# autoimpedance.net
KiCad netlist of a schematic drawn in EAGLE
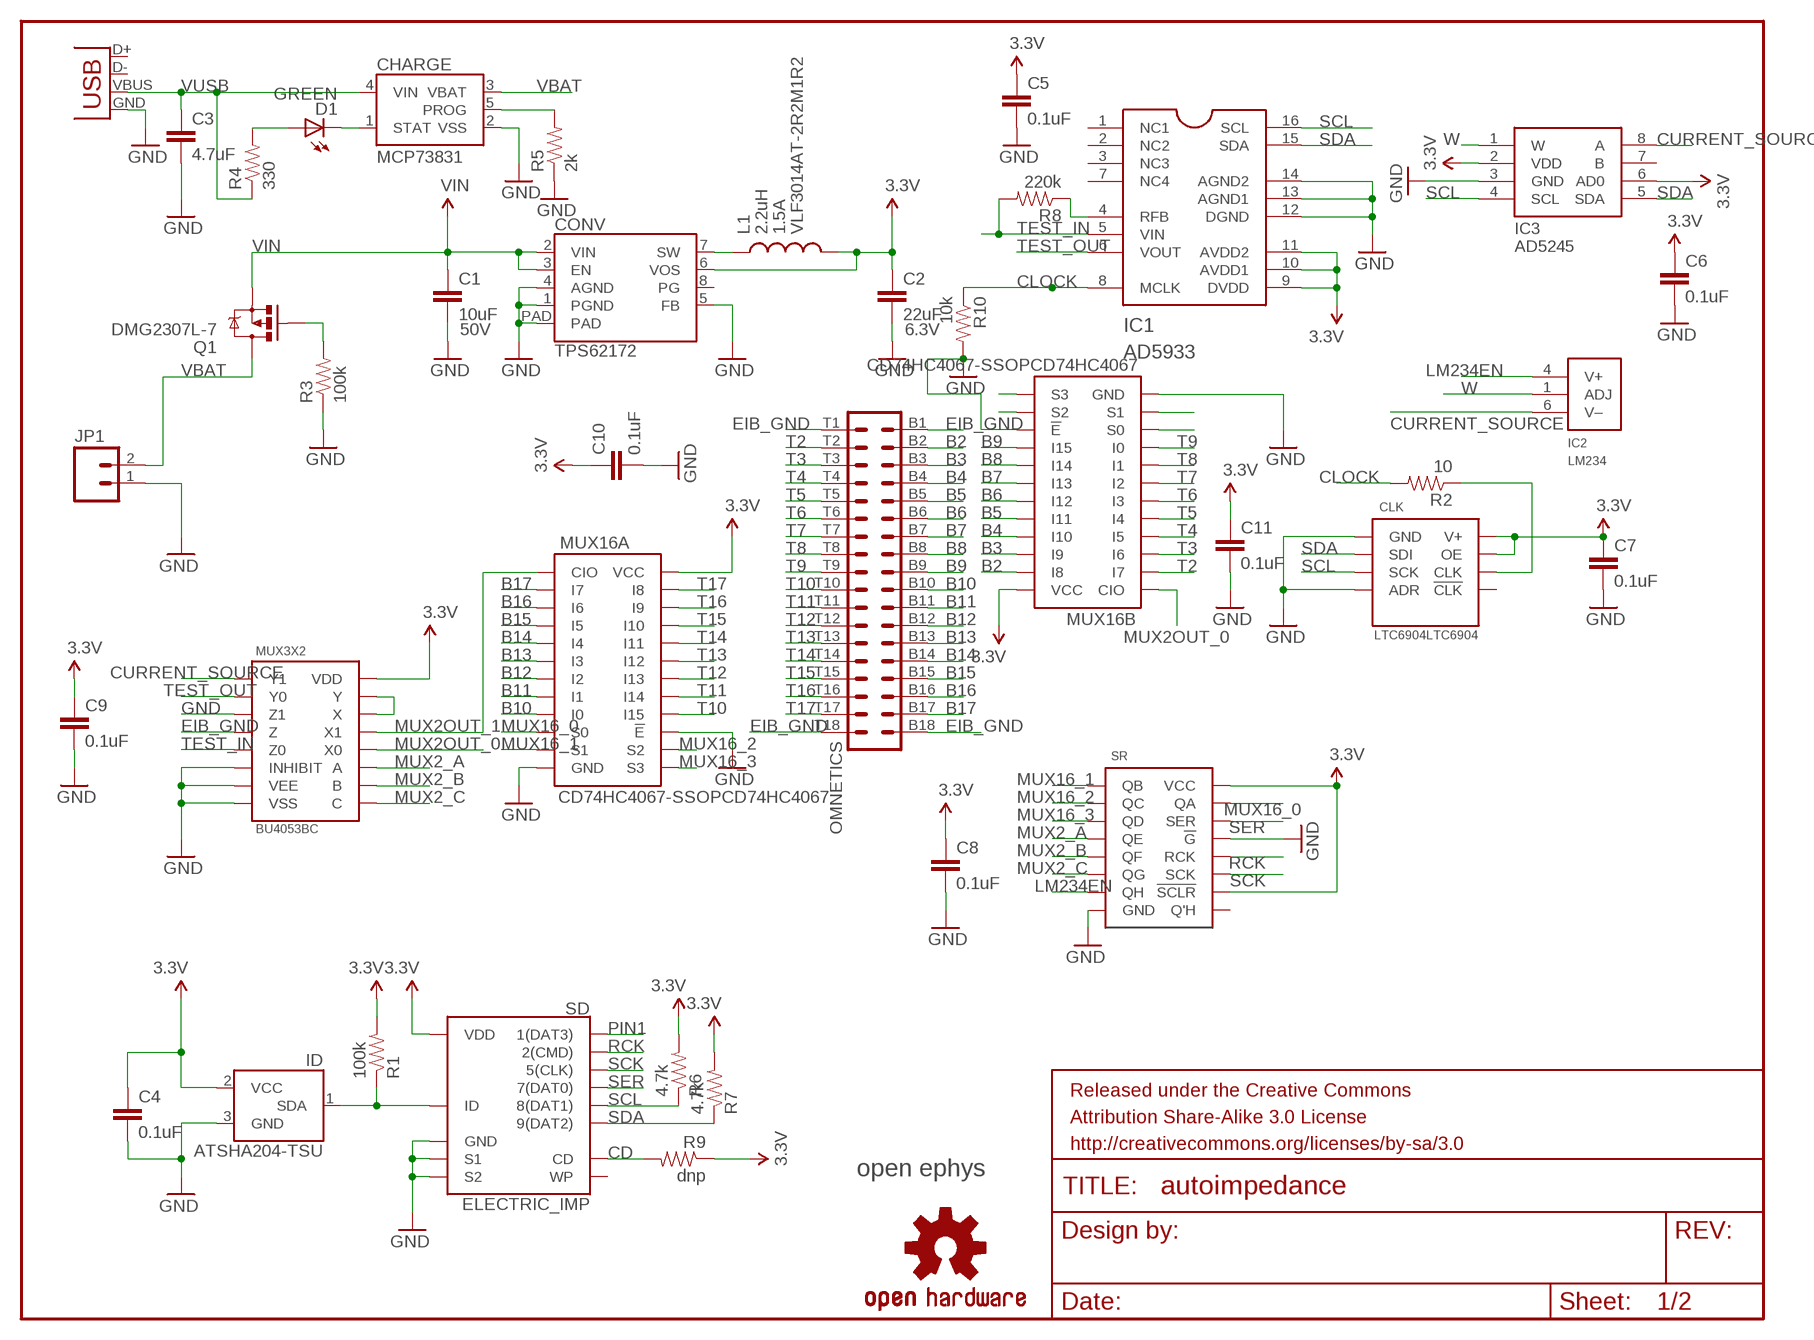
[diagram p0: schematic, sheet 1]

(export (version "E")
  (design (tool "Eeschema 10.0.6"))
  (components
    (comp (ref "C1")
      (value "10uF")
      (footprint "eagle-import:1210")
      (libsource (lib "eagle-import") (part "SparkFun-Passives_CAP1210"))
    )
    (comp (ref "C2")
      (value "22uF")
      (footprint "eagle-import:0805")
      (libsource (lib "eagle-import") (part "SparkFun-Passives_CAP0805"))
    )
    (comp (ref "C3")
      (value "4.7uF")
      (footprint "eagle-import:1210")
      (libsource (lib "eagle-import") (part "SparkFun-Passives_CAP1210"))
    )
    (comp (ref "C4")
      (value "0.1uF")
      (footprint "eagle-import:0603-CAP")
      (libsource (lib "eagle-import") (part "CAP0603-CAP"))
    )
    (comp (ref "C5")
      (value "0.1uF")
      (footprint "eagle-import:0603-CAP")
      (libsource (lib "eagle-import") (part "CAP0603-CAP"))
    )
    (comp (ref "C6")
      (value "0.1uF")
      (footprint "eagle-import:0603-CAP")
      (libsource (lib "eagle-import") (part "CAP0603-CAP"))
    )
    (comp (ref "C7")
      (value "0.1uF")
      (footprint "eagle-import:0603-CAP")
      (libsource (lib "eagle-import") (part "CAP0603-CAP"))
    )
    (comp (ref "C8")
      (value "0.1uF")
      (footprint "eagle-import:0603-CAP")
      (libsource (lib "eagle-import") (part "CAP0603-CAP"))
    )
    (comp (ref "C9")
      (value "0.1uF")
      (footprint "eagle-import:0603-CAP")
      (libsource (lib "eagle-import") (part "CAP0603-CAP"))
    )
    (comp (ref "C10")
      (value "0.1uF")
      (footprint "eagle-import:0603-CAP")
      (libsource (lib "eagle-import") (part "CAP0603-CAP"))
    )
    (comp (ref "C11")
      (value "0.1uF")
      (footprint "eagle-import:0603-CAP")
      (libsource (lib "eagle-import") (part "CAP0603-CAP"))
    )
    (comp (ref "CHARGE")
      (value "MCP73831")
      (footprint "eagle-import:SOT23-5")
      (libsource (lib "eagle-import") (part "MCP73831"))
    )
    (comp (ref "CLK")
      (value "LTC6904LTC6904")
      (footprint "eagle-import:MSOP08")
      (libsource (lib "eagle-import") (part "LTC6904LTC6904"))
    )
    (comp (ref "CONV")
      (value "TPS62172")
      (footprint "eagle-import:WSON-8-PAD")
      (libsource (lib "eagle-import") (part "TPS62172"))
    )
    (comp (ref "D1")
      (value "GREEN")
      (footprint "eagle-import:LED-0603")
      (libsource (lib "eagle-import") (part "LED-GREEN0603"))
    )
    (comp (ref "FRAME1")
      (value "FRAME-LETTER")
      (footprint "eagle-import:CREATIVE_COMMONS")
      (libsource (lib "eagle-import") (part "FRAME-LETTER"))
    )
    (comp (ref "IC1")
      (value "AD5933")
      (footprint "eagle-import:AD5933")
      (libsource (lib "eagle-import") (part "AD5933"))
    )
    (comp (ref "IC2")
      (value "LM234")
      (footprint "eagle-import:LM234")
      (libsource (lib "eagle-import") (part "LM234"))
    )
    (comp (ref "IC3")
      (value "AD5245")
      (footprint "eagle-import:AD5245")
      (libsource (lib "eagle-import") (part "AD5245"))
    )
    (comp (ref "ID")
      (value "ATSHA204-TSU")
      (footprint "eagle-import:SOT23-3")
      (libsource (lib "eagle-import") (part "ATSHA204-TSU"))
    )
    (comp (ref "JP1")
      (value "M02SMD")
      (footprint "eagle-import:1X02_SMD")
      (libsource (lib "eagle-import") (part "M02SMD"))
    )
    (comp (ref "L1")
      (value "2.2uH")
      (footprint "eagle-import:VLF4012A")
      (libsource (lib "eagle-import") (part "INDUCTORVLF4012A"))
    )
    (comp (ref "MUX3X2")
      (value "BU4053BC")
      (footprint "eagle-import:SSOP16")
      (libsource (lib "eagle-import") (part "BU4053BC"))
    )
    (comp (ref "MUX16A")
      (value "CD74HC4067-SSOPCD74HC4067")
      (footprint "eagle-import:SSOP24")
      (libsource (lib "eagle-import") (part "CD74HC4067-SSOPCD74HC4067"))
    )
    (comp (ref "MUX16B")
      (value "CD74HC4067-SSOPCD74HC4067")
      (footprint "eagle-import:SSOP24")
      (libsource (lib "eagle-import") (part "CD74HC4067-SSOPCD74HC4067"))
    )
    (comp (ref "OMNETICS")
      (value "OMNETICS_A79025")
      (footprint "eagle-import:OMNETICS_A79025")
      (libsource (lib "eagle-import") (part "OMNETICS_A79025"))
    )
    (comp (ref "Q1")
      (value "DMG2307L-7")
      (footprint "eagle-import:SOT23-3")
      (libsource (lib "eagle-import") (part "MOSFET-PCHANNELSMD"))
    )
    (comp (ref "R1")
      (value "100k")
      (footprint "eagle-import:0402-RES")
      (libsource (lib "eagle-import") (part "RESISTOR0402-RES"))
    )
    (comp (ref "R2")
      (value "10")
      (footprint "eagle-import:0402-RES")
      (libsource (lib "eagle-import") (part "RESISTOR0402-RES"))
    )
    (comp (ref "R3")
      (value "100k")
      (footprint "eagle-import:0402-RES")
      (libsource (lib "eagle-import") (part "RESISTOR0402-RES"))
    )
    (comp (ref "R4")
      (value "330")
      (footprint "eagle-import:0402-RES")
      (libsource (lib "eagle-import") (part "RESISTOR0402-RES"))
    )
    (comp (ref "R5")
      (value "2k")
      (footprint "eagle-import:0402-RES")
      (libsource (lib "eagle-import") (part "RESISTOR0402-RES"))
    )
    (comp (ref "R6")
      (value "4.7k")
      (footprint "eagle-import:0402-RES")
      (libsource (lib "eagle-import") (part "RESISTOR0402-RES"))
    )
    (comp (ref "R7")
      (value "4.7k")
      (footprint "eagle-import:0402-RES")
      (libsource (lib "eagle-import") (part "RESISTOR0402-RES"))
    )
    (comp (ref "R8")
      (value "220k")
      (footprint "eagle-import:0402-RES")
      (libsource (lib "eagle-import") (part "RESISTOR0402-RES"))
    )
    (comp (ref "R9")
      (value "dnp")
      (footprint "eagle-import:0402-RES")
      (libsource (lib "eagle-import") (part "RESISTOR0402-RES"))
    )
    (comp (ref "R10")
      (value "10k")
      (footprint "eagle-import:0402-RES")
      (libsource (lib "eagle-import") (part "RESISTOR0402-RES"))
    )
    (comp (ref "SD")
      (value "ELECTRIC_IMP")
      (footprint "eagle-import:SD_MMC_SOCKET")
      (libsource (lib "eagle-import") (part "ELECTRIC_IMP"))
    )
    (comp (ref "SR")
      (value "MM74HC595MM74HC595")
      (footprint "eagle-import:TSSOP16")
      (libsource (lib "eagle-import") (part "MM74HC595MM74HC595"))
    )
    (comp (ref "U$5")
      (value "OSHW-LOGOS")
      (footprint "eagle-import:OSHW-LOGO-S")
      (libsource (lib "eagle-import") (part "OSHW-LOGOS"))
    )
    (comp (ref "U$7")
      (value "OPEN_EPHYS_LOGO")
      (footprint "eagle-import:OPEN_EPHYS_LOGO")
      (libsource (lib "eagle-import") (part "OPEN_EPHYS_LOGO"))
    )
    (comp (ref "USB")
      (value "USBSMD")
      (footprint "eagle-import:USB-MINIB")
      (libsource (lib "eagle-import") (part "USBSMD"))
    )
  )
  (nets
    (net (code "1") (name "3.3V") (class "Default")
      (node (ref "C10") (pin "1") (pinfunction "1_1") (pintype "passive"))
      (node (ref "C11") (pin "1") (pinfunction "1_1") (pintype "passive"))
      (node (ref "C2") (pin "1") (pinfunction "1_1") (pintype "passive"))
      (node (ref "C4") (pin "1") (pinfunction "1_1") (pintype "passive"))
      (node (ref "C5") (pin "1") (pinfunction "1_1") (pintype "passive"))
      (node (ref "C6") (pin "1") (pinfunction "1_1") (pintype "passive"))
      (node (ref "C7") (pin "1") (pinfunction "1_1") (pintype "passive"))
      (node (ref "C8") (pin "1") (pinfunction "1_1") (pintype "passive"))
      (node (ref "C9") (pin "1") (pinfunction "1_1") (pintype "passive"))
      (node (ref "CLK") (pin "7") (pinfunction "OE_7") (pintype "bidirectional"))
      (node (ref "CLK") (pin "8") (pinfunction "V+_8") (pintype "power_in"))
      (node (ref "CONV") (pin "6") (pinfunction "VOS_6") (pintype "bidirectional"))
      (node (ref "IC1") (pin "10") (pinfunction "AVDD1_10") (pintype "bidirectional"))
      (node (ref "IC1") (pin "11") (pinfunction "AVDD2_11") (pintype "bidirectional"))
      (node (ref "IC1") (pin "9") (pinfunction "DVDD_9") (pintype "bidirectional"))
      (node (ref "IC3") (pin "2") (pinfunction "VDD_2") (pintype "bidirectional"))
      (node (ref "IC3") (pin "6") (pinfunction "AD0_6") (pintype "bidirectional"))
      (node (ref "ID") (pin "2") (pinfunction "VCC_2") (pintype "bidirectional"))
      (node (ref "L1") (pin "P$2") (pinfunction "2_P$2") (pintype "passive"))
      (node (ref "MUX16A") (pin "24") (pinfunction "VCC_24") (pintype "power_in"))
      (node (ref "MUX16B") (pin "24") (pinfunction "VCC_24") (pintype "power_in"))
      (node (ref "MUX3X2") (pin "16") (pinfunction "VDD_16") (pintype "input"))
      (node (ref "R1") (pin "2") (pinfunction "2_2") (pintype "passive"))
      (node (ref "R6") (pin "2") (pinfunction "2_2") (pintype "passive"))
      (node (ref "R7") (pin "2") (pinfunction "2_2") (pintype "passive"))
      (node (ref "R9") (pin "1") (pinfunction "1_1") (pintype "passive"))
      (node (ref "SD") (pin "4") (pinfunction "VDD_4") (pintype "bidirectional"))
      (node (ref "SR") (pin "10") (pinfunction "~{SCLR}_10") (pintype "bidirectional"))
      (node (ref "SR") (pin "16") (pinfunction "VCC_16") (pintype "power_in"))
    )
    (net (code "2") (name "B2") (class "Default")
      (node (ref "MUX16B") (pin "23") (pinfunction "I8_23") (pintype "bidirectional"))
      (node (ref "OMNETICS") (pin "B2") (pinfunction "B2_B2") (pintype "passive"))
    )
    (net (code "3") (name "B3") (class "Default")
      (node (ref "MUX16B") (pin "22") (pinfunction "I9_22") (pintype "bidirectional"))
      (node (ref "OMNETICS") (pin "B3") (pinfunction "B3_B3") (pintype "passive"))
    )
    (net (code "4") (name "B4") (class "Default")
      (node (ref "MUX16B") (pin "21") (pinfunction "I10_21") (pintype "bidirectional"))
      (node (ref "OMNETICS") (pin "B4") (pinfunction "B4_B4") (pintype "passive"))
    )
    (net (code "5") (name "B5") (class "Default")
      (node (ref "MUX16B") (pin "20") (pinfunction "I11_20") (pintype "bidirectional"))
      (node (ref "OMNETICS") (pin "B5") (pinfunction "B5_B5") (pintype "passive"))
    )
    (net (code "6") (name "B6") (class "Default")
      (node (ref "MUX16B") (pin "19") (pinfunction "I12_19") (pintype "bidirectional"))
      (node (ref "OMNETICS") (pin "B6") (pinfunction "B6_B6") (pintype "passive"))
    )
    (net (code "7") (name "B7") (class "Default")
      (node (ref "MUX16B") (pin "18") (pinfunction "I13_18") (pintype "bidirectional"))
      (node (ref "OMNETICS") (pin "B7") (pinfunction "B7_B7") (pintype "passive"))
    )
    (net (code "8") (name "B8") (class "Default")
      (node (ref "MUX16B") (pin "17") (pinfunction "I14_17") (pintype "bidirectional"))
      (node (ref "OMNETICS") (pin "B8") (pinfunction "B8_B8") (pintype "passive"))
    )
    (net (code "9") (name "B9") (class "Default")
      (node (ref "MUX16B") (pin "16") (pinfunction "I15_16") (pintype "bidirectional"))
      (node (ref "OMNETICS") (pin "B9") (pinfunction "B9_B9") (pintype "passive"))
    )
    (net (code "10") (name "B10") (class "Default")
      (node (ref "MUX16A") (pin "9") (pinfunction "I0_9") (pintype "bidirectional"))
      (node (ref "OMNETICS") (pin "B10") (pinfunction "B10_B10") (pintype "passive"))
    )
    (net (code "11") (name "B11") (class "Default")
      (node (ref "MUX16A") (pin "8") (pinfunction "I1_8") (pintype "bidirectional"))
      (node (ref "OMNETICS") (pin "B11") (pinfunction "B11_B11") (pintype "passive"))
    )
    (net (code "12") (name "B12") (class "Default")
      (node (ref "MUX16A") (pin "7") (pinfunction "I2_7") (pintype "bidirectional"))
      (node (ref "OMNETICS") (pin "B12") (pinfunction "B12_B12") (pintype "passive"))
    )
    (net (code "13") (name "B13") (class "Default")
      (node (ref "MUX16A") (pin "6") (pinfunction "I3_6") (pintype "bidirectional"))
      (node (ref "OMNETICS") (pin "B13") (pinfunction "B13_B13") (pintype "passive"))
    )
    (net (code "14") (name "B14") (class "Default")
      (node (ref "MUX16A") (pin "5") (pinfunction "I4_5") (pintype "bidirectional"))
      (node (ref "OMNETICS") (pin "B14") (pinfunction "B14_B14") (pintype "passive"))
    )
    (net (code "15") (name "B15") (class "Default")
      (node (ref "MUX16A") (pin "4") (pinfunction "I5_4") (pintype "bidirectional"))
      (node (ref "OMNETICS") (pin "B15") (pinfunction "B15_B15") (pintype "passive"))
    )
    (net (code "16") (name "B16") (class "Default")
      (node (ref "MUX16A") (pin "3") (pinfunction "I6_3") (pintype "bidirectional"))
      (node (ref "OMNETICS") (pin "B16") (pinfunction "B16_B16") (pintype "passive"))
    )
    (net (code "17") (name "B17") (class "Default")
      (node (ref "MUX16A") (pin "2") (pinfunction "I7_2") (pintype "bidirectional"))
      (node (ref "OMNETICS") (pin "B17") (pinfunction "B17_B17") (pintype "passive"))
    )
    (net (code "18") (name "CD") (class "Default")
      (node (ref "R9") (pin "2") (pinfunction "2_2") (pintype "passive"))
      (node (ref "SD") (pin "CD") (pinfunction "CD_CD") (pintype "bidirectional"))
    )
    (net (code "19") (name "CLOCK") (class "Default")
      (node (ref "IC1") (pin "8") (pinfunction "MCLK_8") (pintype "bidirectional"))
      (node (ref "R10") (pin "1") (pinfunction "1_1") (pintype "passive"))
      (node (ref "R2") (pin "2") (pinfunction "2_2") (pintype "passive"))
    )
    (net (code "20") (name "CURRENT_SOURCE") (class "Default")
      (node (ref "IC2") (pin "6") (pinfunction "V–_6") (pintype "bidirectional"))
      (node (ref "IC3") (pin "8") (pinfunction "A_8") (pintype "bidirectional"))
      (node (ref "MUX3X2") (pin "1") (pinfunction "Y1_1") (pintype "bidirectional"))
    )
    (net (code "21") (name "EIB_GND") (class "Default")
      (node (ref "MUX3X2") (pin "4") (pinfunction "Z_4") (pintype "bidirectional"))
      (node (ref "OMNETICS") (pin "B1") (pinfunction "B1_B1") (pintype "passive"))
      (node (ref "OMNETICS") (pin "B18") (pinfunction "B18_B18") (pintype "passive"))
      (node (ref "OMNETICS") (pin "T1") (pinfunction "T1_T1") (pintype "passive"))
      (node (ref "OMNETICS") (pin "T18") (pinfunction "T18_T18") (pintype "passive"))
    )
    (net (code "22") (name "GND") (class "Default")
      (node (ref "C1") (pin "2") (pinfunction "2_2") (pintype "passive"))
      (node (ref "C10") (pin "2") (pinfunction "2_2") (pintype "passive"))
      (node (ref "C11") (pin "2") (pinfunction "2_2") (pintype "passive"))
      (node (ref "C2") (pin "2") (pinfunction "2_2") (pintype "passive"))
      (node (ref "C3") (pin "2") (pinfunction "2_2") (pintype "passive"))
      (node (ref "C4") (pin "2") (pinfunction "2_2") (pintype "passive"))
      (node (ref "C5") (pin "2") (pinfunction "2_2") (pintype "passive"))
      (node (ref "C6") (pin "2") (pinfunction "2_2") (pintype "passive"))
      (node (ref "C7") (pin "2") (pinfunction "2_2") (pintype "passive"))
      (node (ref "C8") (pin "2") (pinfunction "2_2") (pintype "passive"))
      (node (ref "C9") (pin "2") (pinfunction "2_2") (pintype "passive"))
      (node (ref "CHARGE") (pin "2") (pinfunction "VSS_2") (pintype "power_in"))
      (node (ref "CLK") (pin "1") (pinfunction "GND_1") (pintype "power_in"))
      (node (ref "CLK") (pin "4") (pinfunction "ADR_4") (pintype "bidirectional"))
      (node (ref "CONV") (pin "1") (pinfunction "PGND_1") (pintype "bidirectional"))
      (node (ref "CONV") (pin "4") (pinfunction "AGND_4") (pintype "bidirectional"))
      (node (ref "CONV") (pin "5") (pinfunction "FB_5") (pintype "bidirectional"))
      (node (ref "CONV") (pin "PAD") (pinfunction "PAD_PAD") (pintype "bidirectional"))
      (node (ref "IC1") (pin "12") (pinfunction "DGND_12") (pintype "bidirectional"))
      (node (ref "IC1") (pin "13") (pinfunction "AGND1_13") (pintype "bidirectional"))
      (node (ref "IC1") (pin "14") (pinfunction "AGND2_14") (pintype "bidirectional"))
      (node (ref "IC3") (pin "3") (pinfunction "GND_3") (pintype "bidirectional"))
      (node (ref "ID") (pin "3") (pinfunction "GND_3") (pintype "bidirectional"))
      (node (ref "JP1") (pin "1") (pinfunction "1_1") (pintype "passive"))
      (node (ref "MUX16A") (pin "12") (pinfunction "GND_12") (pintype "power_in"))
      (node (ref "MUX16A") (pin "15") (pinfunction "~{E}_15") (pintype "bidirectional"))
      (node (ref "MUX16B") (pin "12") (pinfunction "GND_12") (pintype "power_in"))
      (node (ref "MUX16B") (pin "15") (pinfunction "~{E}_15") (pintype "bidirectional"))
      (node (ref "MUX3X2") (pin "3") (pinfunction "Z1_3") (pintype "bidirectional"))
      (node (ref "MUX3X2") (pin "6") (pinfunction "INHIBIT_6") (pintype "bidirectional"))
      (node (ref "MUX3X2") (pin "7") (pinfunction "VEE_7") (pintype "power_in"))
      (node (ref "MUX3X2") (pin "8") (pinfunction "VSS_8") (pintype "power_in"))
      (node (ref "R10") (pin "2") (pinfunction "2_2") (pintype "passive"))
      (node (ref "R3") (pin "1") (pinfunction "1_1") (pintype "passive"))
      (node (ref "R5") (pin "1") (pinfunction "1_1") (pintype "passive"))
      (node (ref "SD") (pin "3") (pinfunction "GND_3") (pintype "bidirectional"))
      (node (ref "SD") (pin "S1") (pinfunction "S1_S1") (pintype "bidirectional"))
      (node (ref "SD") (pin "S2") (pinfunction "S2_S2") (pintype "bidirectional"))
      (node (ref "SR") (pin "13") (pinfunction "~{G}_13") (pintype "bidirectional"))
      (node (ref "SR") (pin "8") (pinfunction "GND_8") (pintype "power_in"))
      (node (ref "USB") (pin "GND") (pinfunction "GND_GND") (pintype "bidirectional"))
    )
    (net (code "23") (name "LM234EN") (class "Default")
      (node (ref "IC2") (pin "4") (pinfunction "V+_4") (pintype "bidirectional"))
      (node (ref "SR") (pin "7") (pinfunction "QH_7") (pintype "output"))
    )
    (net (code "24") (name "MUX2OUT_0") (class "Default")
      (node (ref "MUX16B") (pin "1") (pinfunction "CIO_1") (pintype "bidirectional"))
      (node (ref "MUX3X2") (pin "12") (pinfunction "X0_12") (pintype "bidirectional"))
    )
    (net (code "25") (name "MUX2OUT_1") (class "Default")
      (node (ref "MUX16A") (pin "1") (pinfunction "CIO_1") (pintype "bidirectional"))
      (node (ref "MUX3X2") (pin "13") (pinfunction "X1_13") (pintype "bidirectional"))
    )
    (net (code "26") (name "MUX2_A") (class "Default")
      (node (ref "MUX3X2") (pin "11") (pinfunction "A_11") (pintype "bidirectional"))
      (node (ref "SR") (pin "4") (pinfunction "QE_4") (pintype "output"))
    )
    (net (code "27") (name "MUX2_B") (class "Default")
      (node (ref "MUX3X2") (pin "10") (pinfunction "B_10") (pintype "bidirectional"))
      (node (ref "SR") (pin "5") (pinfunction "QF_5") (pintype "output"))
    )
    (net (code "28") (name "MUX2_C") (class "Default")
      (node (ref "MUX3X2") (pin "9") (pinfunction "C_9") (pintype "power_in"))
      (node (ref "SR") (pin "6") (pinfunction "QG_6") (pintype "output"))
    )
    (net (code "29") (name "MUX16_0") (class "Default")
      (node (ref "MUX16A") (pin "10") (pinfunction "S0_10") (pintype "bidirectional"))
      (node (ref "MUX16B") (pin "10") (pinfunction "S0_10") (pintype "bidirectional"))
      (node (ref "SR") (pin "15") (pinfunction "QA_15") (pintype "output"))
    )
    (net (code "30") (name "MUX16_1") (class "Default")
      (node (ref "MUX16A") (pin "11") (pinfunction "S1_11") (pintype "bidirectional"))
      (node (ref "MUX16B") (pin "11") (pinfunction "S1_11") (pintype "bidirectional"))
      (node (ref "SR") (pin "1") (pinfunction "QB_1") (pintype "output"))
    )
    (net (code "31") (name "MUX16_2") (class "Default")
      (node (ref "MUX16A") (pin "14") (pinfunction "S2_14") (pintype "bidirectional"))
      (node (ref "MUX16B") (pin "14") (pinfunction "S2_14") (pintype "bidirectional"))
      (node (ref "SR") (pin "2") (pinfunction "QC_2") (pintype "output"))
    )
    (net (code "32") (name "MUX16_3") (class "Default")
      (node (ref "MUX16A") (pin "13") (pinfunction "S3_13") (pintype "bidirectional"))
      (node (ref "MUX16B") (pin "13") (pinfunction "S3_13") (pintype "bidirectional"))
      (node (ref "SR") (pin "3") (pinfunction "QD_3") (pintype "output"))
    )
    (net (code "33") (name "Net-(CHARGE-PROG)") (class "Default")
      (node (ref "CHARGE") (pin "5") (pinfunction "PROG_5") (pintype "input"))
      (node (ref "R5") (pin "2") (pinfunction "2_2") (pintype "passive"))
    )
    (net (code "34") (name "Net-(CHARGE-STAT)") (class "Default")
      (node (ref "CHARGE") (pin "1") (pinfunction "STAT_1") (pintype "output"))
      (node (ref "D1") (pin "C") (pinfunction "C_C") (pintype "passive"))
    )
    (net (code "35") (name "Net-(CLK-CLK)") (class "Default")
      (node (ref "CLK") (pin "6") (pinfunction "CLK_6") (pintype "output"))
      (node (ref "R2") (pin "1") (pinfunction "1_1") (pintype "passive"))
    )
    (net (code "36") (name "Net-(CONV-SW)") (class "Default")
      (node (ref "CONV") (pin "7") (pinfunction "SW_7") (pintype "bidirectional"))
      (node (ref "L1") (pin "P$1") (pinfunction "1_P$1") (pintype "passive"))
    )
    (net (code "37") (name "Net-(D1-PadA)") (class "Default")
      (node (ref "D1") (pin "A") (pinfunction "A_A") (pintype "passive"))
      (node (ref "R4") (pin "2") (pinfunction "2_2") (pintype "passive"))
    )
    (net (code "38") (name "Net-(IC1-RFB)") (class "Default")
      (node (ref "IC1") (pin "4") (pinfunction "RFB_4") (pintype "bidirectional"))
      (node (ref "R8") (pin "1") (pinfunction "1_1") (pintype "passive"))
    )
    (net (code "39") (name "Net-(ID-SDA)") (class "Default")
      (node (ref "ID") (pin "1") (pinfunction "SDA_1") (pintype "bidirectional"))
      (node (ref "R1") (pin "1") (pinfunction "1_1") (pintype "passive"))
      (node (ref "SD") (pin "6") (pinfunction "ID_6") (pintype "bidirectional"))
    )
    (net (code "40") (name "Net-(MUX3X2-X)") (class "Default")
      (node (ref "MUX3X2") (pin "14") (pinfunction "X_14") (pintype "bidirectional"))
      (node (ref "MUX3X2") (pin "15") (pinfunction "Y_15") (pintype "bidirectional"))
    )
    (net (code "41") (name "Net-(Q1-G)") (class "Default")
      (node (ref "Q1") (pin "1") (pinfunction "G_1") (pintype "passive"))
      (node (ref "R3") (pin "2") (pinfunction "2_2") (pintype "passive"))
    )
    (net (code "42") (name "PIN1") (class "Default")
      (node (ref "SD") (pin "1") (pinfunction "1(DAT3)_1") (pintype "bidirectional"))
    )
    (net (code "43") (name "RCK") (class "Default")
      (node (ref "SD") (pin "2") (pinfunction "2(CMD)_2") (pintype "bidirectional"))
      (node (ref "SR") (pin "12") (pinfunction "RCK_12") (pintype "input"))
    )
    (net (code "44") (name "SCK") (class "Default")
      (node (ref "SD") (pin "5") (pinfunction "5(CLK)_5") (pintype "bidirectional"))
      (node (ref "SR") (pin "11") (pinfunction "SCK_11") (pintype "input"))
    )
    (net (code "45") (name "SCL") (class "Default")
      (node (ref "CLK") (pin "3") (pinfunction "SCK_3") (pintype "input"))
      (node (ref "IC1") (pin "16") (pinfunction "SCL_16") (pintype "bidirectional"))
      (node (ref "IC3") (pin "4") (pinfunction "SCL_4") (pintype "bidirectional"))
      (node (ref "R6") (pin "1") (pinfunction "1_1") (pintype "passive"))
      (node (ref "SD") (pin "8") (pinfunction "8(DAT1)_8") (pintype "bidirectional"))
    )
    (net (code "46") (name "SDA") (class "Default")
      (node (ref "CLK") (pin "2") (pinfunction "SDI_2") (pintype "input"))
      (node (ref "IC1") (pin "15") (pinfunction "SDA_15") (pintype "bidirectional"))
      (node (ref "IC3") (pin "5") (pinfunction "SDA_5") (pintype "bidirectional"))
      (node (ref "R7") (pin "1") (pinfunction "1_1") (pintype "passive"))
      (node (ref "SD") (pin "9") (pinfunction "9(DAT2)_9") (pintype "bidirectional"))
    )
    (net (code "47") (name "SER") (class "Default")
      (node (ref "SD") (pin "7") (pinfunction "7(DAT0)_7") (pintype "bidirectional"))
      (node (ref "SR") (pin "14") (pinfunction "SER_14") (pintype "input"))
    )
    (net (code "48") (name "T2") (class "Default")
      (node (ref "MUX16B") (pin "2") (pinfunction "I7_2") (pintype "bidirectional"))
      (node (ref "OMNETICS") (pin "T2") (pinfunction "T2_T2") (pintype "passive"))
    )
    (net (code "49") (name "T3") (class "Default")
      (node (ref "MUX16B") (pin "3") (pinfunction "I6_3") (pintype "bidirectional"))
      (node (ref "OMNETICS") (pin "T3") (pinfunction "T3_T3") (pintype "passive"))
    )
    (net (code "50") (name "T4") (class "Default")
      (node (ref "MUX16B") (pin "4") (pinfunction "I5_4") (pintype "bidirectional"))
      (node (ref "OMNETICS") (pin "T4") (pinfunction "T4_T4") (pintype "passive"))
    )
    (net (code "51") (name "T5") (class "Default")
      (node (ref "MUX16B") (pin "5") (pinfunction "I4_5") (pintype "bidirectional"))
      (node (ref "OMNETICS") (pin "T5") (pinfunction "T5_T5") (pintype "passive"))
    )
    (net (code "52") (name "T6") (class "Default")
      (node (ref "MUX16B") (pin "6") (pinfunction "I3_6") (pintype "bidirectional"))
      (node (ref "OMNETICS") (pin "T6") (pinfunction "T6_T6") (pintype "passive"))
    )
    (net (code "53") (name "T7") (class "Default")
      (node (ref "MUX16B") (pin "7") (pinfunction "I2_7") (pintype "bidirectional"))
      (node (ref "OMNETICS") (pin "T7") (pinfunction "T7_T7") (pintype "passive"))
    )
    (net (code "54") (name "T8") (class "Default")
      (node (ref "MUX16B") (pin "8") (pinfunction "I1_8") (pintype "bidirectional"))
      (node (ref "OMNETICS") (pin "T8") (pinfunction "T8_T8") (pintype "passive"))
    )
    (net (code "55") (name "T9") (class "Default")
      (node (ref "MUX16B") (pin "9") (pinfunction "I0_9") (pintype "bidirectional"))
      (node (ref "OMNETICS") (pin "T9") (pinfunction "T9_T9") (pintype "passive"))
    )
    (net (code "56") (name "T10") (class "Default")
      (node (ref "MUX16A") (pin "16") (pinfunction "I15_16") (pintype "bidirectional"))
      (node (ref "OMNETICS") (pin "T10") (pinfunction "T10_T10") (pintype "passive"))
    )
    (net (code "57") (name "T11") (class "Default")
      (node (ref "MUX16A") (pin "17") (pinfunction "I14_17") (pintype "bidirectional"))
      (node (ref "OMNETICS") (pin "T11") (pinfunction "T11_T11") (pintype "passive"))
    )
    (net (code "58") (name "T12") (class "Default")
      (node (ref "MUX16A") (pin "18") (pinfunction "I13_18") (pintype "bidirectional"))
      (node (ref "OMNETICS") (pin "T12") (pinfunction "T12_T12") (pintype "passive"))
    )
    (net (code "59") (name "T13") (class "Default")
      (node (ref "MUX16A") (pin "19") (pinfunction "I12_19") (pintype "bidirectional"))
      (node (ref "OMNETICS") (pin "T13") (pinfunction "T13_T13") (pintype "passive"))
    )
    (net (code "60") (name "T14") (class "Default")
      (node (ref "MUX16A") (pin "20") (pinfunction "I11_20") (pintype "bidirectional"))
      (node (ref "OMNETICS") (pin "T14") (pinfunction "T14_T14") (pintype "passive"))
    )
    (net (code "61") (name "T15") (class "Default")
      (node (ref "MUX16A") (pin "21") (pinfunction "I10_21") (pintype "bidirectional"))
      (node (ref "OMNETICS") (pin "T15") (pinfunction "T15_T15") (pintype "passive"))
    )
    (net (code "62") (name "T16") (class "Default")
      (node (ref "MUX16A") (pin "22") (pinfunction "I9_22") (pintype "bidirectional"))
      (node (ref "OMNETICS") (pin "T16") (pinfunction "T16_T16") (pintype "passive"))
    )
    (net (code "63") (name "T17") (class "Default")
      (node (ref "MUX16A") (pin "23") (pinfunction "I8_23") (pintype "bidirectional"))
      (node (ref "OMNETICS") (pin "T17") (pinfunction "T17_T17") (pintype "passive"))
    )
    (net (code "64") (name "TEST_IN") (class "Default")
      (node (ref "IC1") (pin "5") (pinfunction "VIN_5") (pintype "bidirectional"))
      (node (ref "MUX3X2") (pin "5") (pinfunction "Z0_5") (pintype "bidirectional"))
      (node (ref "R8") (pin "2") (pinfunction "2_2") (pintype "passive"))
    )
    (net (code "65") (name "TEST_OUT") (class "Default")
      (node (ref "IC1") (pin "6") (pinfunction "VOUT_6") (pintype "bidirectional"))
      (node (ref "MUX3X2") (pin "2") (pinfunction "Y0_2") (pintype "bidirectional"))
    )
    (net (code "66") (name "VBAT") (class "Default")
      (node (ref "CHARGE") (pin "3") (pinfunction "VBAT_3") (pintype "power_in"))
      (node (ref "JP1") (pin "2") (pinfunction "2_2") (pintype "passive"))
      (node (ref "Q1") (pin "3") (pinfunction "D_3") (pintype "passive"))
    )
    (net (code "67") (name "VIN") (class "Default")
      (node (ref "C1") (pin "1") (pinfunction "1_1") (pintype "passive"))
      (node (ref "CONV") (pin "2") (pinfunction "VIN_2") (pintype "bidirectional"))
      (node (ref "CONV") (pin "3") (pinfunction "EN_3") (pintype "bidirectional"))
      (node (ref "Q1") (pin "2") (pinfunction "S_2") (pintype "passive"))
    )
    (net (code "68") (name "VUSB") (class "Default")
      (node (ref "C3") (pin "1") (pinfunction "1_1") (pintype "passive"))
      (node (ref "CHARGE") (pin "4") (pinfunction "VIN_4") (pintype "power_in"))
      (node (ref "R4") (pin "1") (pinfunction "1_1") (pintype "passive"))
      (node (ref "USB") (pin "VBUS") (pinfunction "VBUS_VBUS") (pintype "bidirectional"))
    )
    (net (code "69") (name "W") (class "Default")
      (node (ref "IC2") (pin "1") (pinfunction "ADJ_1") (pintype "bidirectional"))
      (node (ref "IC3") (pin "1") (pinfunction "W_1") (pintype "bidirectional"))
    )
    (net (code "70") (name "unconnected-(CLK-~{CLK}-Pad5)") (class "Default")
      (node (ref "CLK") (pin "5") (pinfunction "~{CLK}_5") (pintype "output"))
    )
    (net (code "71") (name "unconnected-(CONV-PG-Pad8)") (class "Default")
      (node (ref "CONV") (pin "8") (pinfunction "PG_8") (pintype "bidirectional"))
    )
    (net (code "72") (name "unconnected-(IC1-NC1-Pad1)") (class "Default")
      (node (ref "IC1") (pin "1") (pinfunction "NC1_1") (pintype "no_connect"))
    )
    (net (code "73") (name "unconnected-(IC1-NC2-Pad2)") (class "Default")
      (node (ref "IC1") (pin "2") (pinfunction "NC2_2") (pintype "no_connect"))
    )
    (net (code "74") (name "unconnected-(IC1-NC3-Pad3)") (class "Default")
      (node (ref "IC1") (pin "3") (pinfunction "NC3_3") (pintype "no_connect"))
    )
    (net (code "75") (name "unconnected-(IC1-NC4-Pad7)") (class "Default")
      (node (ref "IC1") (pin "7") (pinfunction "NC4_7") (pintype "no_connect"))
    )
    (net (code "76") (name "unconnected-(IC3-B-Pad7)") (class "Default")
      (node (ref "IC3") (pin "7") (pinfunction "B_7") (pintype "bidirectional"))
    )
    (net (code "77") (name "unconnected-(SD-PadWP)") (class "Default")
      (node (ref "SD") (pin "WP") (pinfunction "WP_WP") (pintype "bidirectional"))
    )
    (net (code "78") (name "unconnected-(SR-Q'H-Pad9)") (class "Default")
      (node (ref "SR") (pin "9") (pinfunction "Q'H_9") (pintype "output"))
    )
    (net (code "79") (name "unconnected-(USB-PadD+)") (class "Default")
      (node (ref "USB") (pin "D+") (pinfunction "D+_D+") (pintype "bidirectional"))
    )
    (net (code "80") (name "unconnected-(USB-PadD-)") (class "Default")
      (node (ref "USB") (pin "D-") (pinfunction "D-_D-") (pintype "bidirectional"))
    )
  )
)
